# 2_byte_output.net
KiCad netlist of a schematic drawn in EAGLE
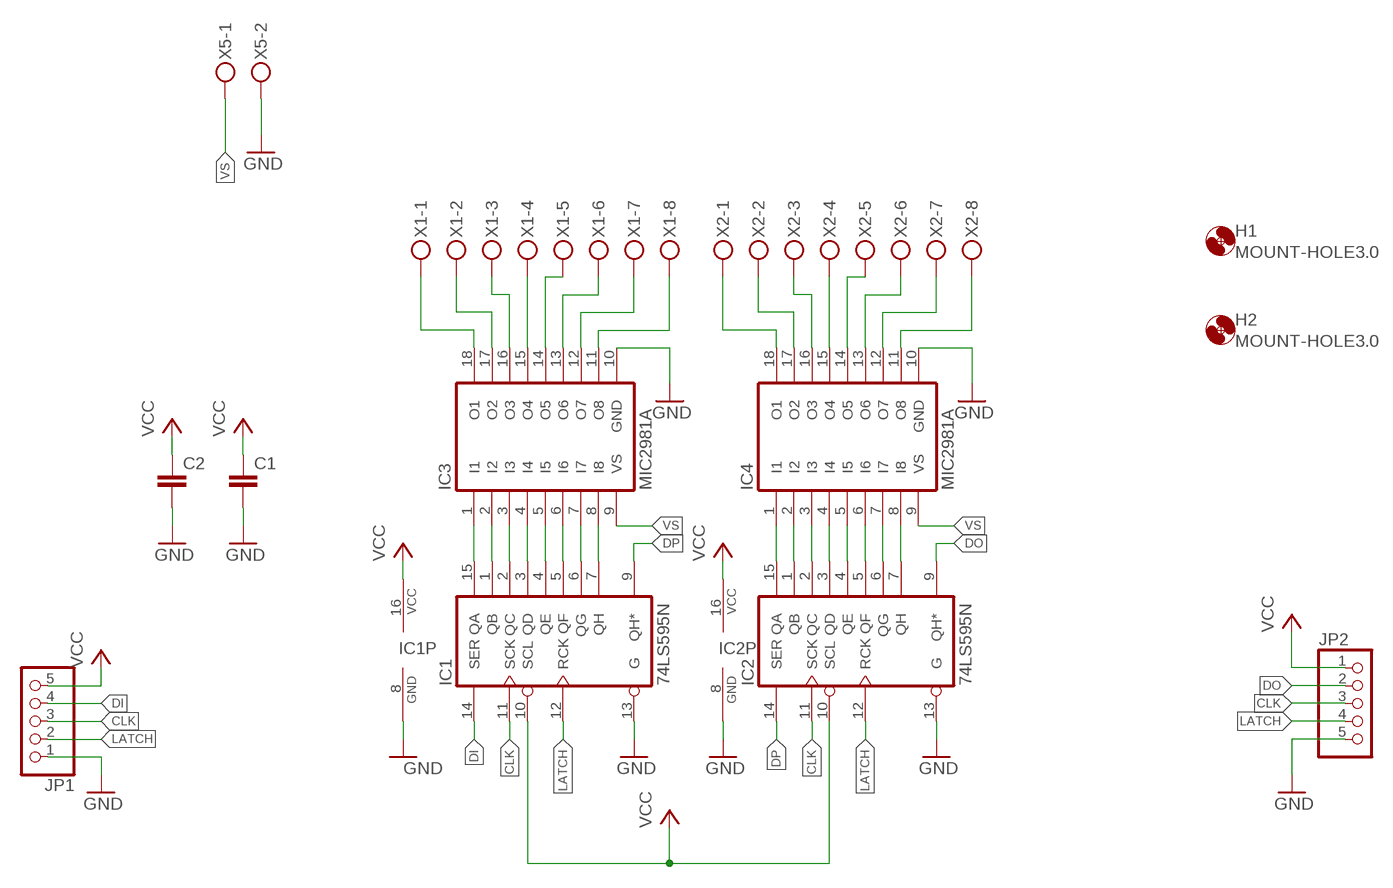
[diagram p0: schematic, sheet 1]

(export (version "E")
  (design (tool "Eeschema 10.0.6"))
  (components
    (comp (ref "C1")
      (value "C-EU050-035X075")
      (footprint "eagle-import:C050-035X075")
      (libsource (lib "eagle-import") (part "C-EU050-035X075"))
    )
    (comp (ref "C2")
      (value "C-EU050-035X075")
      (footprint "eagle-import:C050-035X075")
      (libsource (lib "eagle-import") (part "C-EU050-035X075"))
    )
    (comp (ref "H1")
      (value "MOUNT-HOLE3.0")
      (footprint "eagle-import:3,0")
      (libsource (lib "eagle-import") (part "MOUNT-HOLE3.0"))
    )
    (comp (ref "H2")
      (value "MOUNT-HOLE3.0")
      (footprint "eagle-import:3,0")
      (libsource (lib "eagle-import") (part "MOUNT-HOLE3.0"))
    )
    (comp (ref "IC1")
      (value "74LS595N")
      (footprint "eagle-import:DIL16")
      (libsource (lib "eagle-import") (part "74595NLS"))
    )
    (comp (ref "IC2")
      (value "74LS595N")
      (footprint "eagle-import:DIL16")
      (libsource (lib "eagle-import") (part "74595NLS"))
    )
    (comp (ref "IC3")
      (value "MIC2981A")
      (footprint "eagle-import:DIL18")
      (libsource (lib "eagle-import") (part "UDN298A1"))
    )
    (comp (ref "IC4")
      (value "MIC2981A")
      (footprint "eagle-import:DIL18")
      (libsource (lib "eagle-import") (part "UDN298A1"))
    )
    (comp (ref "JP1")
      (value "PINHD-1X5/90")
      (footprint "eagle-import:1X05_90")
      (libsource (lib "eagle-import") (part "PINHD-1X5/90"))
    )
    (comp (ref "JP2")
      (value "PINHD-1X5/90")
      (footprint "eagle-import:1X05_90")
      (libsource (lib "eagle-import") (part "PINHD-1X5/90"))
    )
    (comp (ref "X1")
      (value "MKDSN1,5/8-5,08")
      (footprint "eagle-import:MKDSN1,5_8-5,08")
      (libsource (lib "eagle-import") (part "MKDSN1,5/8-5,08"))
    )
    (comp (ref "X2")
      (value "MKDSN1,5/8-5,08")
      (footprint "eagle-import:MKDSN1,5_8-5,08")
      (libsource (lib "eagle-import") (part "MKDSN1,5/8-5,08"))
    )
    (comp (ref "X5")
      (value "MKDSN1,5/2-5,08")
      (footprint "eagle-import:MKDSN1,5_2-5,08")
      (libsource (lib "eagle-import") (part "MKDSN1,5/2-5,08"))
    )
  )
  (nets
    (net (code "1") (name "CLK") (class "Default")
      (node (ref "IC1") (pin "11") (pinfunction "SCK_11") (pintype "input"))
      (node (ref "IC2") (pin "11") (pinfunction "SCK_11") (pintype "input"))
      (node (ref "JP1") (pin "3") (pinfunction "3_3") (pintype "passive"))
      (node (ref "JP2") (pin "3") (pinfunction "3_3") (pintype "passive"))
    )
    (net (code "2") (name "DI") (class "Default")
      (node (ref "IC1") (pin "14") (pinfunction "SER_14") (pintype "input"))
      (node (ref "JP1") (pin "4") (pinfunction "4_4") (pintype "passive"))
    )
    (net (code "3") (name "DO") (class "Default")
      (node (ref "IC2") (pin "9") (pinfunction "QH*_9") (pintype "tri_state"))
      (node (ref "JP2") (pin "2") (pinfunction "2_2") (pintype "passive"))
    )
    (net (code "4") (name "DP") (class "Default")
      (node (ref "IC1") (pin "9") (pinfunction "QH*_9") (pintype "tri_state"))
      (node (ref "IC2") (pin "14") (pinfunction "SER_14") (pintype "input"))
    )
    (net (code "5") (name "GND") (class "Default")
      (node (ref "C1") (pin "2") (pinfunction "2_2") (pintype "passive"))
      (node (ref "C2") (pin "2") (pinfunction "2_2") (pintype "passive"))
      (node (ref "IC1") (pin "13") (pinfunction "G_13") (pintype "input"))
      (node (ref "IC1") (pin "8") (pinfunction "GND_8") (pintype "power_in"))
      (node (ref "IC2") (pin "13") (pinfunction "G_13") (pintype "input"))
      (node (ref "IC2") (pin "8") (pinfunction "GND_8") (pintype "power_in"))
      (node (ref "IC3") (pin "10") (pinfunction "GND_10") (pintype "power_in"))
      (node (ref "IC4") (pin "10") (pinfunction "GND_10") (pintype "power_in"))
      (node (ref "JP1") (pin "1") (pinfunction "1_1") (pintype "passive"))
      (node (ref "JP2") (pin "5") (pinfunction "5_5") (pintype "passive"))
      (node (ref "X5") (pin "2") (pinfunction "KL_2") (pintype "passive"))
    )
    (net (code "6") (name "LATCH") (class "Default")
      (node (ref "IC1") (pin "12") (pinfunction "RCK_12") (pintype "input"))
      (node (ref "IC2") (pin "12") (pinfunction "RCK_12") (pintype "input"))
      (node (ref "JP1") (pin "2") (pinfunction "2_2") (pintype "passive"))
      (node (ref "JP2") (pin "4") (pinfunction "4_4") (pintype "passive"))
    )
    (net (code "7") (name "Net-(IC1A-QA)") (class "Default")
      (node (ref "IC1") (pin "15") (pinfunction "QA_15") (pintype "tri_state"))
      (node (ref "IC3") (pin "1") (pinfunction "I1_1") (pintype "input"))
    )
    (net (code "8") (name "Net-(IC1A-QB)") (class "Default")
      (node (ref "IC1") (pin "1") (pinfunction "QB_1") (pintype "tri_state"))
      (node (ref "IC3") (pin "2") (pinfunction "I2_2") (pintype "input"))
    )
    (net (code "9") (name "Net-(IC1A-QC)") (class "Default")
      (node (ref "IC1") (pin "2") (pinfunction "QC_2") (pintype "tri_state"))
      (node (ref "IC3") (pin "3") (pinfunction "I3_3") (pintype "input"))
    )
    (net (code "10") (name "Net-(IC1A-QD)") (class "Default")
      (node (ref "IC1") (pin "3") (pinfunction "QD_3") (pintype "tri_state"))
      (node (ref "IC3") (pin "4") (pinfunction "I4_4") (pintype "input"))
    )
    (net (code "11") (name "Net-(IC1A-QE)") (class "Default")
      (node (ref "IC1") (pin "4") (pinfunction "QE_4") (pintype "tri_state"))
      (node (ref "IC3") (pin "5") (pinfunction "I5_5") (pintype "input"))
    )
    (net (code "12") (name "Net-(IC1A-QF)") (class "Default")
      (node (ref "IC1") (pin "5") (pinfunction "QF_5") (pintype "tri_state"))
      (node (ref "IC3") (pin "6") (pinfunction "I6_6") (pintype "input"))
    )
    (net (code "13") (name "Net-(IC1A-QG)") (class "Default")
      (node (ref "IC1") (pin "6") (pinfunction "QG_6") (pintype "tri_state"))
      (node (ref "IC3") (pin "7") (pinfunction "I7_7") (pintype "input"))
    )
    (net (code "14") (name "Net-(IC1A-QH)") (class "Default")
      (node (ref "IC1") (pin "7") (pinfunction "QH_7") (pintype "tri_state"))
      (node (ref "IC3") (pin "8") (pinfunction "I8_8") (pintype "input"))
    )
    (net (code "15") (name "Net-(IC2A-QA)") (class "Default")
      (node (ref "IC2") (pin "15") (pinfunction "QA_15") (pintype "tri_state"))
      (node (ref "IC4") (pin "1") (pinfunction "I1_1") (pintype "input"))
    )
    (net (code "16") (name "Net-(IC2A-QB)") (class "Default")
      (node (ref "IC2") (pin "1") (pinfunction "QB_1") (pintype "tri_state"))
      (node (ref "IC4") (pin "2") (pinfunction "I2_2") (pintype "input"))
    )
    (net (code "17") (name "Net-(IC2A-QC)") (class "Default")
      (node (ref "IC2") (pin "2") (pinfunction "QC_2") (pintype "tri_state"))
      (node (ref "IC4") (pin "3") (pinfunction "I3_3") (pintype "input"))
    )
    (net (code "18") (name "Net-(IC2A-QD)") (class "Default")
      (node (ref "IC2") (pin "3") (pinfunction "QD_3") (pintype "tri_state"))
      (node (ref "IC4") (pin "4") (pinfunction "I4_4") (pintype "input"))
    )
    (net (code "19") (name "Net-(IC2A-QE)") (class "Default")
      (node (ref "IC2") (pin "4") (pinfunction "QE_4") (pintype "tri_state"))
      (node (ref "IC4") (pin "5") (pinfunction "I5_5") (pintype "input"))
    )
    (net (code "20") (name "Net-(IC2A-QF)") (class "Default")
      (node (ref "IC2") (pin "5") (pinfunction "QF_5") (pintype "tri_state"))
      (node (ref "IC4") (pin "6") (pinfunction "I6_6") (pintype "input"))
    )
    (net (code "21") (name "Net-(IC2A-QG)") (class "Default")
      (node (ref "IC2") (pin "6") (pinfunction "QG_6") (pintype "tri_state"))
      (node (ref "IC4") (pin "7") (pinfunction "I7_7") (pintype "input"))
    )
    (net (code "22") (name "Net-(IC2A-QH)") (class "Default")
      (node (ref "IC2") (pin "7") (pinfunction "QH_7") (pintype "tri_state"))
      (node (ref "IC4") (pin "8") (pinfunction "I8_8") (pintype "input"))
    )
    (net (code "23") (name "Net-(IC3-O1)") (class "Default")
      (node (ref "IC3") (pin "18") (pinfunction "O1_18") (pintype "open_collector"))
      (node (ref "X1") (pin "1") (pinfunction "KL_1") (pintype "passive"))
    )
    (net (code "24") (name "Net-(IC3-O2)") (class "Default")
      (node (ref "IC3") (pin "17") (pinfunction "O2_17") (pintype "open_collector"))
      (node (ref "X1") (pin "2") (pinfunction "KL_2") (pintype "passive"))
    )
    (net (code "25") (name "Net-(IC3-O3)") (class "Default")
      (node (ref "IC3") (pin "16") (pinfunction "O3_16") (pintype "open_collector"))
      (node (ref "X1") (pin "3") (pinfunction "KL_3") (pintype "passive"))
    )
    (net (code "26") (name "Net-(IC3-O4)") (class "Default")
      (node (ref "IC3") (pin "15") (pinfunction "O4_15") (pintype "open_collector"))
      (node (ref "X1") (pin "4") (pinfunction "KL_4") (pintype "passive"))
    )
    (net (code "27") (name "Net-(IC3-O5)") (class "Default")
      (node (ref "IC3") (pin "14") (pinfunction "O5_14") (pintype "open_collector"))
      (node (ref "X1") (pin "5") (pinfunction "KL_5") (pintype "passive"))
    )
    (net (code "28") (name "Net-(IC3-O6)") (class "Default")
      (node (ref "IC3") (pin "13") (pinfunction "O6_13") (pintype "open_collector"))
      (node (ref "X1") (pin "6") (pinfunction "KL_6") (pintype "passive"))
    )
    (net (code "29") (name "Net-(IC3-O7)") (class "Default")
      (node (ref "IC3") (pin "12") (pinfunction "O7_12") (pintype "open_collector"))
      (node (ref "X1") (pin "7") (pinfunction "KL_7") (pintype "passive"))
    )
    (net (code "30") (name "Net-(IC3-O8)") (class "Default")
      (node (ref "IC3") (pin "11") (pinfunction "O8_11") (pintype "open_collector"))
      (node (ref "X1") (pin "8") (pinfunction "KL_8") (pintype "passive"))
    )
    (net (code "31") (name "Net-(IC4-O1)") (class "Default")
      (node (ref "IC4") (pin "18") (pinfunction "O1_18") (pintype "open_collector"))
      (node (ref "X2") (pin "1") (pinfunction "KL_1") (pintype "passive"))
    )
    (net (code "32") (name "Net-(IC4-O2)") (class "Default")
      (node (ref "IC4") (pin "17") (pinfunction "O2_17") (pintype "open_collector"))
      (node (ref "X2") (pin "2") (pinfunction "KL_2") (pintype "passive"))
    )
    (net (code "33") (name "Net-(IC4-O3)") (class "Default")
      (node (ref "IC4") (pin "16") (pinfunction "O3_16") (pintype "open_collector"))
      (node (ref "X2") (pin "3") (pinfunction "KL_3") (pintype "passive"))
    )
    (net (code "34") (name "Net-(IC4-O4)") (class "Default")
      (node (ref "IC4") (pin "15") (pinfunction "O4_15") (pintype "open_collector"))
      (node (ref "X2") (pin "4") (pinfunction "KL_4") (pintype "passive"))
    )
    (net (code "35") (name "Net-(IC4-O5)") (class "Default")
      (node (ref "IC4") (pin "14") (pinfunction "O5_14") (pintype "open_collector"))
      (node (ref "X2") (pin "5") (pinfunction "KL_5") (pintype "passive"))
    )
    (net (code "36") (name "Net-(IC4-O6)") (class "Default")
      (node (ref "IC4") (pin "13") (pinfunction "O6_13") (pintype "open_collector"))
      (node (ref "X2") (pin "6") (pinfunction "KL_6") (pintype "passive"))
    )
    (net (code "37") (name "Net-(IC4-O7)") (class "Default")
      (node (ref "IC4") (pin "12") (pinfunction "O7_12") (pintype "open_collector"))
      (node (ref "X2") (pin "7") (pinfunction "KL_7") (pintype "passive"))
    )
    (net (code "38") (name "Net-(IC4-O8)") (class "Default")
      (node (ref "IC4") (pin "11") (pinfunction "O8_11") (pintype "open_collector"))
      (node (ref "X2") (pin "8") (pinfunction "KL_8") (pintype "passive"))
    )
    (net (code "39") (name "VCC") (class "Default")
      (node (ref "C1") (pin "1") (pinfunction "1_1") (pintype "passive"))
      (node (ref "C2") (pin "1") (pinfunction "1_1") (pintype "passive"))
      (node (ref "IC1") (pin "10") (pinfunction "SCL_10") (pintype "input"))
      (node (ref "IC1") (pin "16") (pinfunction "VCC_16") (pintype "power_in"))
      (node (ref "IC2") (pin "10") (pinfunction "SCL_10") (pintype "input"))
      (node (ref "IC2") (pin "16") (pinfunction "VCC_16") (pintype "power_in"))
      (node (ref "JP1") (pin "5") (pinfunction "5_5") (pintype "passive"))
      (node (ref "JP2") (pin "1") (pinfunction "1_1") (pintype "passive"))
    )
    (net (code "40") (name "VS") (class "Default")
      (node (ref "IC3") (pin "9") (pinfunction "VS_9") (pintype "passive"))
      (node (ref "IC4") (pin "9") (pinfunction "VS_9") (pintype "passive"))
      (node (ref "X5") (pin "1") (pinfunction "KL_1") (pintype "passive"))
    )
  )
)
